# FuseBlock.net
KiCad netlist of a schematic drawn in EasyEDA
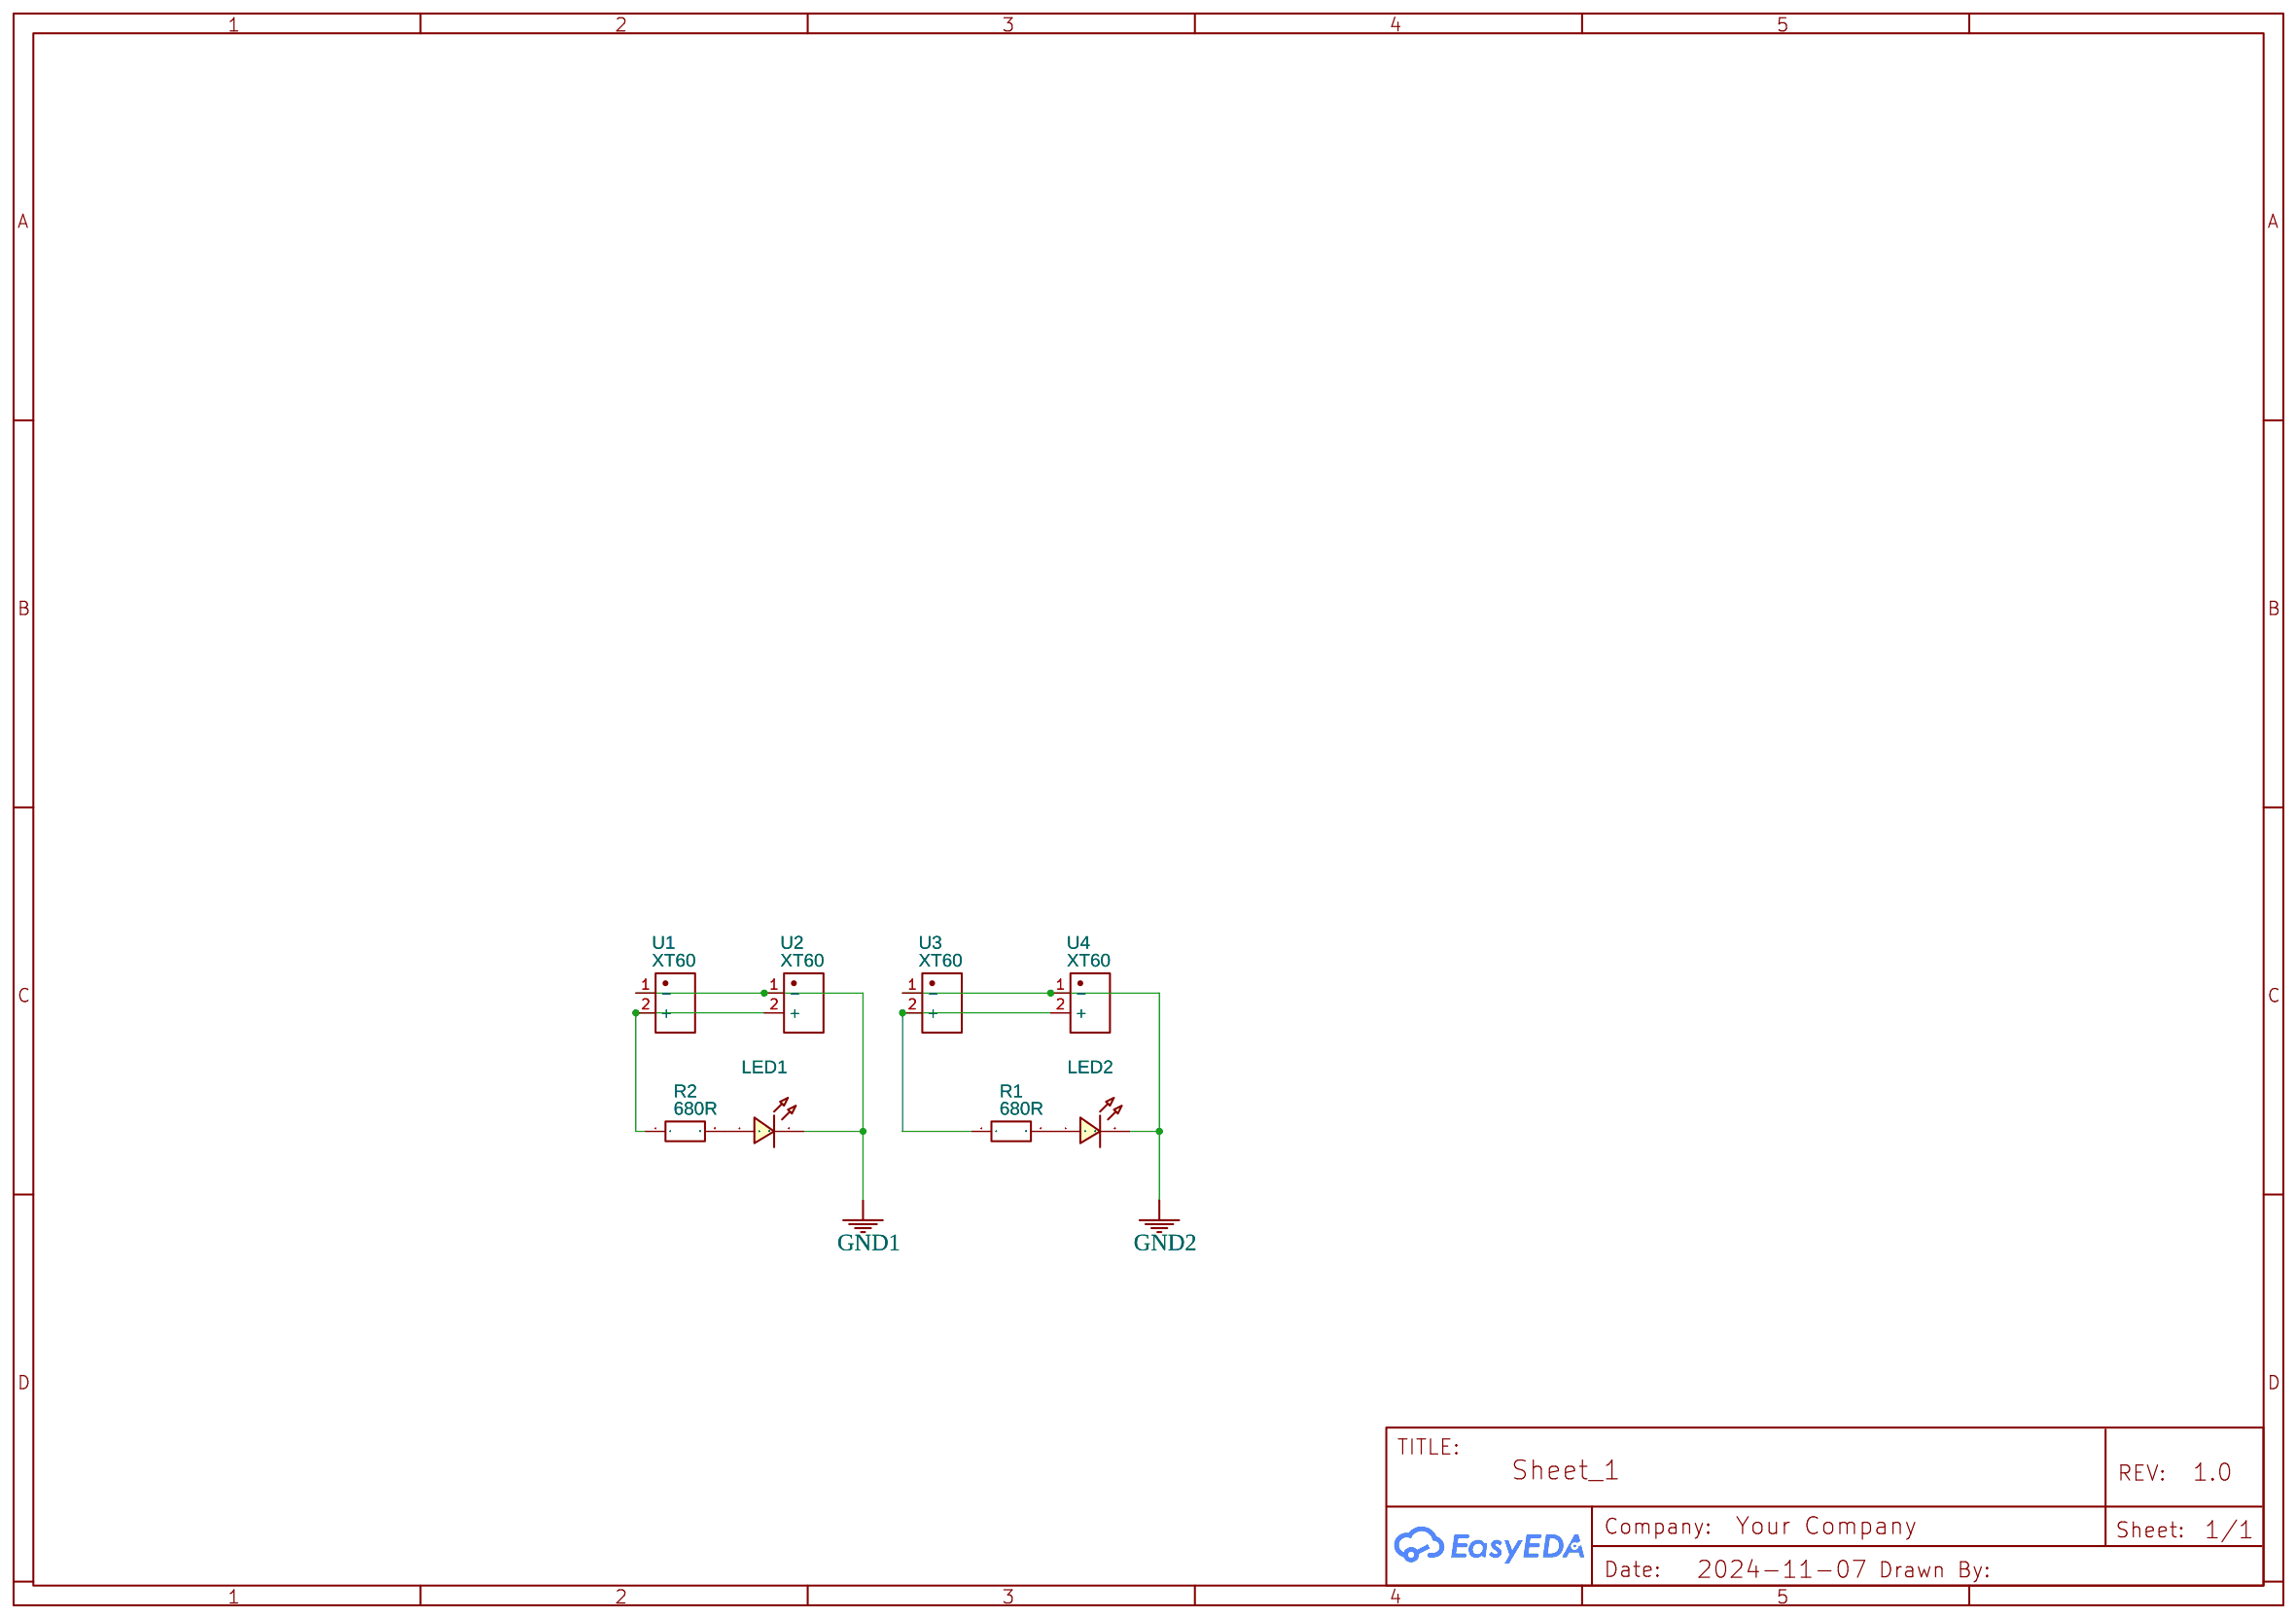
[diagram p0: schematic sheet]

(export (version "E")
  (design (tool "Eeschema 10.0.6"))
  (components
    (comp (ref "LED1")
      (value "LED-0603_R")
      (fields
        (field (name "Manufacturer Part") "19-217/R6C-AL1M2VY/3T")
        (field (name "Manufacturer") "EVERLIGHT(台湾亿光)")
      )
      (libsource (lib "") (part "LED-0603_R"))
    )
    (comp (ref "LED2")
      (value "LED-0603_R")
      (fields
        (field (name "Manufacturer Part") "19-217/R6C-AL1M2VY/3T")
        (field (name "Manufacturer") "EVERLIGHT(台湾亿光)")
      )
      (libsource (lib "") (part "LED-0603_R"))
    )
    (comp (ref "R1") (value "680R") (libsource (lib "") (part "R_0603_EU")))
    (comp (ref "R2") (value "680R") (libsource (lib "") (part "R_0603_EU")))
    (comp (ref "U1")
      (value "XT60")
      (fields (field (name "Manufacturer") "AMASS(艾迈斯)"))
      (libsource (lib "") (part "XT60"))
    )
    (comp (ref "U2")
      (value "XT60")
      (fields (field (name "Manufacturer") "AMASS(艾迈斯)"))
      (libsource (lib "") (part "XT60"))
    )
    (comp (ref "U3")
      (value "XT60")
      (fields (field (name "Manufacturer") "AMASS(艾迈斯)"))
      (libsource (lib "") (part "XT60"))
    )
    (comp (ref "U4")
      (value "XT60")
      (fields (field (name "Manufacturer") "AMASS(艾迈斯)"))
      (libsource (lib "") (part "XT60"))
    )
  )
  (nets
    (net (code "1") (name "GND1") (class "Default")
      (node (ref "LED1") (pin "2") (pinfunction "2_2") (pintype "unspecified"))
      (node (ref "U1") (pin "1") (pinfunction "-_1") (pintype "unspecified"))
      (node (ref "U2") (pin "1") (pinfunction "-_1") (pintype "unspecified"))
    )
    (net (code "2") (name "GND2") (class "Default")
      (node (ref "LED2") (pin "2") (pinfunction "2_2") (pintype "unspecified"))
      (node (ref "U3") (pin "1") (pinfunction "-_1") (pintype "unspecified"))
      (node (ref "U4") (pin "1") (pinfunction "-_1") (pintype "unspecified"))
    )
    (net (code "3") (name "Net-(LED1-Pad1)") (class "Default")
      (node (ref "LED1") (pin "1") (pinfunction "1_1") (pintype "unspecified"))
      (node (ref "R2") (pin "2") (pinfunction "2_2") (pintype "unspecified"))
    )
    (net (code "4") (name "Net-(LED2-Pad1)") (class "Default")
      (node (ref "LED2") (pin "1") (pinfunction "1_1") (pintype "unspecified"))
      (node (ref "R1") (pin "2") (pinfunction "2_2") (pintype "unspecified"))
    )
    (net (code "5") (name "Net-(U1-+)") (class "Default")
      (node (ref "R2") (pin "1") (pinfunction "1_1") (pintype "unspecified"))
      (node (ref "U1") (pin "2") (pinfunction "+_2") (pintype "unspecified"))
      (node (ref "U2") (pin "2") (pinfunction "+_2") (pintype "unspecified"))
    )
    (net (code "6") (name "Net-(U3-+)") (class "Default")
      (node (ref "R1") (pin "1") (pinfunction "1_1") (pintype "unspecified"))
      (node (ref "U3") (pin "2") (pinfunction "+_2") (pintype "unspecified"))
      (node (ref "U4") (pin "2") (pinfunction "+_2") (pintype "unspecified"))
    )
  )
)
